# RC_Receiver.net
KiCad netlist of a schematic drawn in EAGLE
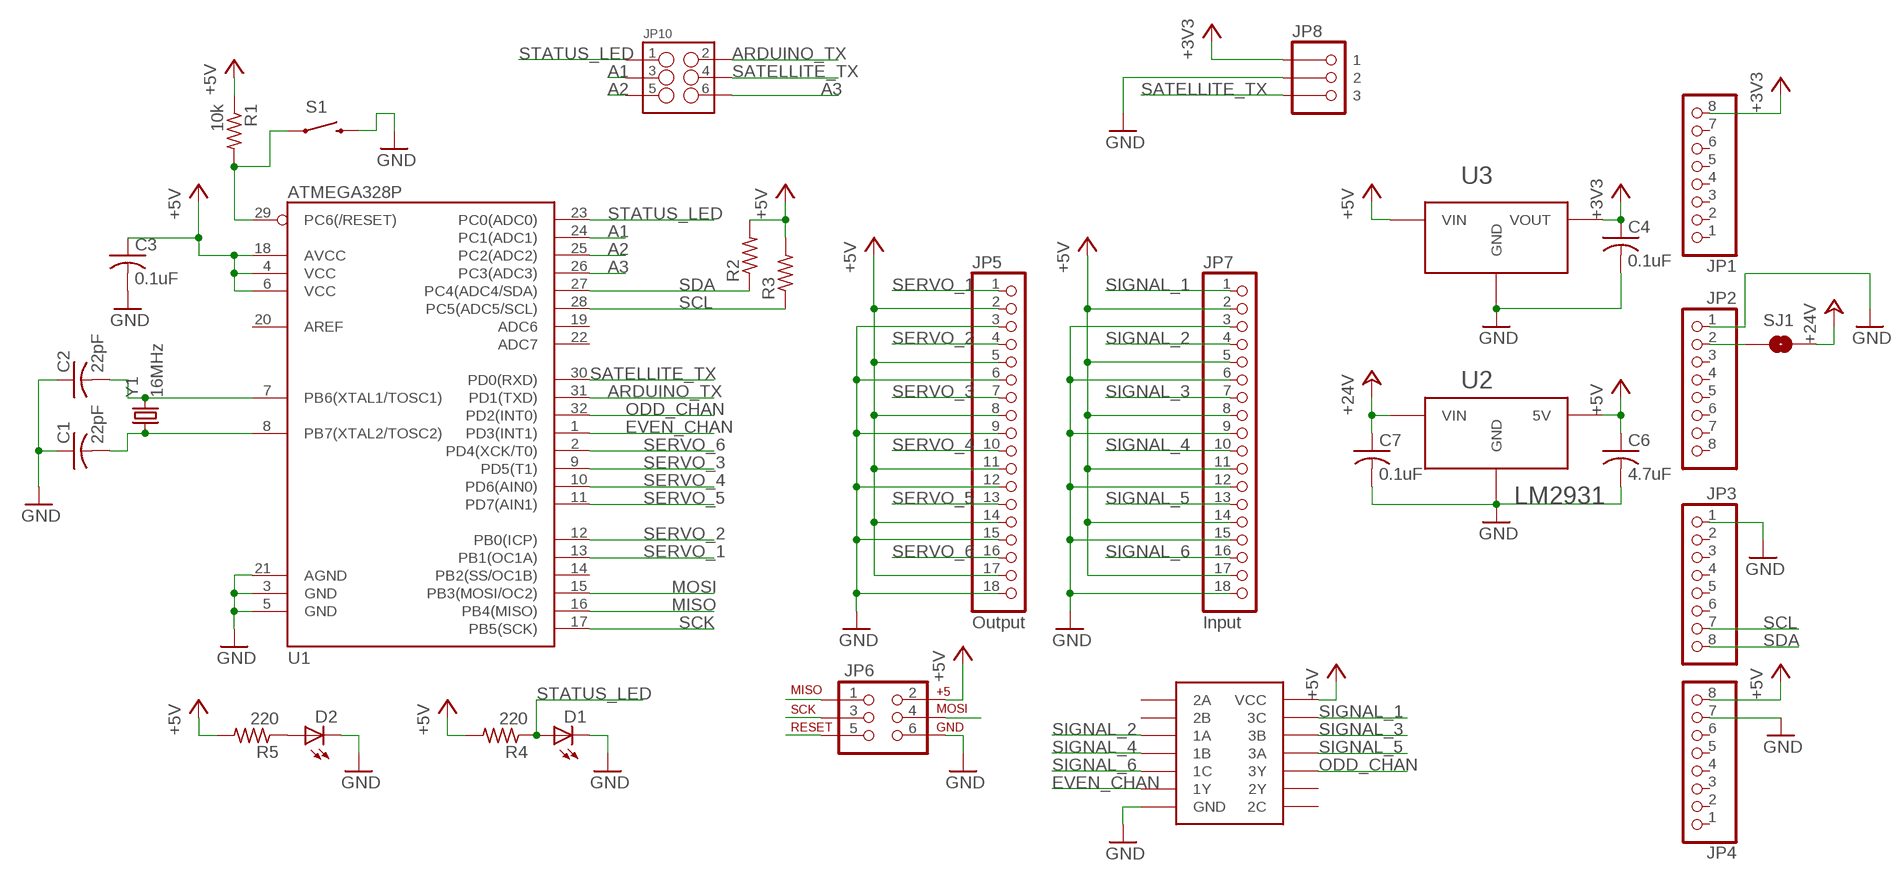
[diagram p0: schematic, sheet 1]

(export (version "E")
  (design (tool "Eeschema 10.0.6"))
  (components
    (comp (ref "C1")
      (value "22pF")
      (footprint "eagle-import:C0603")
      (libsource (lib "eagle-import") (part "C-USC0603"))
    )
    (comp (ref "C2")
      (value "22pF")
      (footprint "eagle-import:C0603")
      (libsource (lib "eagle-import") (part "C-USC0603"))
    )
    (comp (ref "C3")
      (value "0.1uF")
      (footprint "eagle-import:C0603")
      (libsource (lib "eagle-import") (part "C-USC0603"))
    )
    (comp (ref "C4")
      (value "0.1uF")
      (footprint "eagle-import:C0603")
      (libsource (lib "eagle-import") (part "C-USC0603"))
    )
    (comp (ref "C6")
      (value "4.7uF")
      (footprint "eagle-import:C0603")
      (libsource (lib "eagle-import") (part "C-USC0603"))
    )
    (comp (ref "C7")
      (value "0.1uF")
      (footprint "eagle-import:C0603")
      (libsource (lib "eagle-import") (part "C-USC0603"))
    )
    (comp (ref "D1")
      (value "LED-GREENLED-0805_NO_SILK")
      (footprint "eagle-import:LED-0805")
      (libsource (lib "eagle-import") (part "LED-GREENLED-0805_NO_SILK"))
    )
    (comp (ref "D2")
      (value "LED-GREENLED-0805_NO_SILK")
      (footprint "eagle-import:LED-0805")
      (libsource (lib "eagle-import") (part "LED-GREENLED-0805_NO_SILK"))
    )
    (comp (ref "JP1")
      (value "PINHD-1X81X08_NO_SILK")
      (footprint "eagle-import:1X08_NO_SS")
      (libsource (lib "eagle-import") (part "PINHD-1X81X08_NO_SILK"))
    )
    (comp (ref "JP2")
      (value "PINHD-1X81X08_NO_SILK")
      (footprint "eagle-import:1X08_NO_SS")
      (libsource (lib "eagle-import") (part "PINHD-1X81X08_NO_SILK"))
    )
    (comp (ref "JP3")
      (value "PINHD-1X81X08_NO_SILK")
      (footprint "eagle-import:1X08_NO_SS")
      (libsource (lib "eagle-import") (part "PINHD-1X81X08_NO_SILK"))
    )
    (comp (ref "JP4")
      (value "PINHD-1X81X08_NO_SILK")
      (footprint "eagle-import:1X08_NO_SS")
      (libsource (lib "eagle-import") (part "PINHD-1X81X08_NO_SILK"))
    )
    (comp (ref "JP5")
      (value "Output")
      (footprint "eagle-import:3X6_PTH_HEADER")
      (libsource (lib "eagle-import") (part "18_PIN_HEADER3X6_PTH_HEADER"))
    )
    (comp (ref "JP6")
      (value "AVR_SPI_PRG_62X3_LOCK")
      (footprint "eagle-import:2X3_LOCK")
      (libsource (lib "eagle-import") (part "AVR_SPI_PRG_62X3_LOCK"))
    )
    (comp (ref "JP7")
      (value "Input")
      (footprint "eagle-import:3X6_PTH_HEADER")
      (libsource (lib "eagle-import") (part "18_PIN_HEADER3X6_PTH_HEADER"))
    )
    (comp (ref "JP8")
      (value "3-PIN_JST_ZH_PTH_CONNECTORRIGHT_ANGLE_PTH")
      (footprint "eagle-import:3-PIN_JST_ZH_CONNECTOR_TH")
      (fields (field (name "PART#") "455-1670-ND"))
      (libsource (lib "eagle-import") (part "3-PIN_JST_ZH_PTH_CONNECTORRIGHT_ANGLE_PTH"))
    )
    (comp (ref "JP10")
      (value "M03X2NO_SILK")
      (footprint "eagle-import:2X3-NS")
      (libsource (lib "eagle-import") (part "M03X2NO_SILK"))
    )
    (comp (ref "R1")
      (value "10k")
      (footprint "eagle-import:R0603")
      (libsource (lib "eagle-import") (part "R-US_R0603"))
    )
    (comp (ref "R2")
      (value "R-US_R0603")
      (footprint "eagle-import:R0603")
      (libsource (lib "eagle-import") (part "R-US_R0603"))
    )
    (comp (ref "R3")
      (value "R-US_R0603")
      (footprint "eagle-import:R0603")
      (libsource (lib "eagle-import") (part "R-US_R0603"))
    )
    (comp (ref "R4")
      (value "220")
      (footprint "eagle-import:R0603")
      (libsource (lib "eagle-import") (part "R-US_R0603"))
    )
    (comp (ref "R5")
      (value "220")
      (footprint "eagle-import:R0603")
      (libsource (lib "eagle-import") (part "R-US_R0603"))
    )
    (comp (ref "S1")
      (value "SWITCH-MOMENTARY-2SMD")
      (footprint "eagle-import:TACTILE_SWITCH_SMD")
      (libsource (lib "eagle-import") (part "SWITCH-MOMENTARY-2SMD"))
    )
    (comp (ref "SJ1")
      (value "SOLDERJUMPERNC")
      (footprint "eagle-import:SJ_2S")
      (libsource (lib "eagle-import") (part "SOLDERJUMPERNC"))
    )
    (comp (ref "U1")
      (value "ATMEGA328P")
      (footprint "eagle-import:TQFP32-08")
      (libsource (lib "eagle-import") (part "ATMEGA328_SMT"))
    )
    (comp (ref "U2")
      (value "LM2931")
      (footprint "eagle-import:TO263")
      (fields (field (name "PART#") "lm2931"))
      (libsource (lib "eagle-import") (part "LM2931"))
    )
    (comp (ref "U3")
      (value "AP7313SOT23R")
      (footprint "eagle-import:SOT23")
      (fields (field (name "PART#") "AP7313-33SRG-7"))
      (libsource (lib "eagle-import") (part "AP7313SOT23R"))
    )
    (comp (ref "U4")
      (value "C74HC407514-SOIC")
      (footprint "eagle-import:14-SOIC")
      (fields (field (name "PART#") "296-14534-1-ND"))
      (libsource (lib "eagle-import") (part "C74HC407514-SOIC"))
    )
    (comp (ref "Y1")
      (value "16MHz")
      (footprint "eagle-import:CRYSTAL-SMD-5X3")
      (fields (field (name "PART#") "887-1104-1-ND"))
      (libsource (lib "eagle-import") (part "CRYSTAL5X3"))
    )
  )
  (nets
    (net (code "1") (name "+3V3") (class "Default")
      (node (ref "C4") (pin "1") (pinfunction "1_1") (pintype "passive"))
      (node (ref "JP1") (pin "8") (pinfunction "8_8") (pintype "passive"))
      (node (ref "JP8") (pin "P$1") (pinfunction "1_P$1") (pintype "passive"))
      (node (ref "U3") (pin "P$2") (pinfunction "VOUT_P$2") (pintype "bidirectional"))
    )
    (net (code "2") (name "+5V") (class "Default")
      (node (ref "C3") (pin "1") (pinfunction "1_1") (pintype "passive"))
      (node (ref "C6") (pin "1") (pinfunction "1_1") (pintype "passive"))
      (node (ref "JP4") (pin "8") (pinfunction "8_8") (pintype "passive"))
      (node (ref "JP5") (pin "11") (pinfunction "11_11") (pintype "passive"))
      (node (ref "JP5") (pin "14") (pinfunction "14_14") (pintype "passive"))
      (node (ref "JP5") (pin "17") (pinfunction "17_17") (pintype "passive"))
      (node (ref "JP5") (pin "2") (pinfunction "2_2") (pintype "passive"))
      (node (ref "JP5") (pin "5") (pinfunction "5_5") (pintype "passive"))
      (node (ref "JP5") (pin "8") (pinfunction "8_8") (pintype "passive"))
      (node (ref "JP6") (pin "2") (pinfunction "2_2") (pintype "passive"))
      (node (ref "JP7") (pin "11") (pinfunction "11_11") (pintype "passive"))
      (node (ref "JP7") (pin "14") (pinfunction "14_14") (pintype "passive"))
      (node (ref "JP7") (pin "17") (pinfunction "17_17") (pintype "passive"))
      (node (ref "JP7") (pin "2") (pinfunction "2_2") (pintype "passive"))
      (node (ref "JP7") (pin "5") (pinfunction "5_5") (pintype "passive"))
      (node (ref "JP7") (pin "8") (pinfunction "8_8") (pintype "passive"))
      (node (ref "R1") (pin "1") (pinfunction "1_1") (pintype "passive"))
      (node (ref "R2") (pin "2") (pinfunction "2_2") (pintype "passive"))
      (node (ref "R3") (pin "2") (pinfunction "2_2") (pintype "passive"))
      (node (ref "R4") (pin "2") (pinfunction "2_2") (pintype "passive"))
      (node (ref "R5") (pin "2") (pinfunction "2_2") (pintype "passive"))
      (node (ref "U1") (pin "18") (pinfunction "AVCC_18") (pintype "bidirectional"))
      (node (ref "U1") (pin "4") (pinfunction "VCC_4") (pintype "bidirectional"))
      (node (ref "U1") (pin "6") (pinfunction "VCC_6") (pintype "bidirectional"))
      (node (ref "U2") (pin "P$3") (pinfunction "5V_P$3") (pintype "bidirectional"))
      (node (ref "U3") (pin "P$3") (pinfunction "VIN_P$3") (pintype "bidirectional"))
      (node (ref "U4") (pin "P$14") (pinfunction "VCC_P$14") (pintype "power_in"))
    )
    (net (code "3") (name "+24V") (class "Default")
      (node (ref "C7") (pin "1") (pinfunction "1_1") (pintype "passive"))
      (node (ref "SJ1") (pin "2") (pinfunction "2_2") (pintype "passive"))
      (node (ref "U2") (pin "P$2") (pinfunction "VIN_P$2") (pintype "bidirectional"))
    )
    (net (code "4") (name "/A1") (class "Default")
      (node (ref "JP10") (pin "3") (pinfunction "3_3") (pintype "bidirectional"))
      (node (ref "U1") (pin "24") (pinfunction "PC1(ADC1)_24") (pintype "bidirectional"))
    )
    (net (code "5") (name "/A2") (class "Default")
      (node (ref "JP10") (pin "5") (pinfunction "5_5") (pintype "bidirectional"))
      (node (ref "U1") (pin "25") (pinfunction "PC2(ADC2)_25") (pintype "bidirectional"))
    )
    (net (code "6") (name "/A3") (class "Default")
      (node (ref "JP10") (pin "6") (pinfunction "6_6") (pintype "bidirectional"))
      (node (ref "U1") (pin "26") (pinfunction "PC3(ADC3)_26") (pintype "bidirectional"))
    )
    (net (code "7") (name "/ARDUINO_TX") (class "Default")
      (node (ref "JP10") (pin "2") (pinfunction "2_2") (pintype "bidirectional"))
      (node (ref "U1") (pin "31") (pinfunction "PD1(TXD)_31") (pintype "bidirectional"))
    )
    (net (code "8") (name "/EVEN_CHAN") (class "Default")
      (node (ref "U1") (pin "1") (pinfunction "PD3(INT1)_1") (pintype "bidirectional"))
      (node (ref "U4") (pin "P$6") (pinfunction "1Y_P$6") (pintype "bidirectional"))
    )
    (net (code "9") (name "/MISO") (class "Default")
      (node (ref "JP6") (pin "1") (pinfunction "1_1") (pintype "passive"))
      (node (ref "U1") (pin "16") (pinfunction "PB4(MISO)_16") (pintype "bidirectional"))
    )
    (net (code "10") (name "/MOSI") (class "Default")
      (node (ref "JP6") (pin "4") (pinfunction "4_4") (pintype "passive"))
      (node (ref "U1") (pin "15") (pinfunction "PB3(MOSI/OC2)_15") (pintype "bidirectional"))
    )
    (net (code "11") (name "/ODD_CHAN") (class "Default")
      (node (ref "U1") (pin "32") (pinfunction "PD2(INT0)_32") (pintype "bidirectional"))
      (node (ref "U4") (pin "P$10") (pinfunction "3Y_P$10") (pintype "bidirectional"))
    )
    (net (code "12") (name "/RESET") (class "Default")
      (node (ref "JP6") (pin "5") (pinfunction "5_5") (pintype "passive"))
      (node (ref "R1") (pin "2") (pinfunction "2_2") (pintype "passive"))
      (node (ref "S1") (pin "1") (pinfunction "1_1") (pintype "passive"))
      (node (ref "U1") (pin "29") (pinfunction "PC6(/RESET)_29") (pintype "bidirectional"))
    )
    (net (code "13") (name "/SATELLITE_TX") (class "Default")
      (node (ref "JP10") (pin "4") (pinfunction "4_4") (pintype "bidirectional"))
      (node (ref "JP8") (pin "P$3") (pinfunction "3_P$3") (pintype "passive"))
      (node (ref "U1") (pin "30") (pinfunction "PD0(RXD)_30") (pintype "bidirectional"))
    )
    (net (code "14") (name "/SCK") (class "Default")
      (node (ref "JP6") (pin "3") (pinfunction "3_3") (pintype "passive"))
      (node (ref "U1") (pin "17") (pinfunction "PB5(SCK)_17") (pintype "bidirectional"))
    )
    (net (code "15") (name "/SCL") (class "Default")
      (node (ref "JP3") (pin "7") (pinfunction "7_7") (pintype "passive"))
      (node (ref "R3") (pin "1") (pinfunction "1_1") (pintype "passive"))
      (node (ref "U1") (pin "28") (pinfunction "PC5(ADC5/SCL)_28") (pintype "bidirectional"))
    )
    (net (code "16") (name "/SDA") (class "Default")
      (node (ref "JP3") (pin "8") (pinfunction "8_8") (pintype "passive"))
      (node (ref "R2") (pin "1") (pinfunction "1_1") (pintype "passive"))
      (node (ref "U1") (pin "27") (pinfunction "PC4(ADC4/SDA)_27") (pintype "bidirectional"))
    )
    (net (code "17") (name "/SERVO_1") (class "Default")
      (node (ref "JP5") (pin "1") (pinfunction "1_1") (pintype "passive"))
      (node (ref "U1") (pin "13") (pinfunction "PB1(OC1A)_13") (pintype "bidirectional"))
    )
    (net (code "18") (name "/SERVO_2") (class "Default")
      (node (ref "JP5") (pin "4") (pinfunction "4_4") (pintype "passive"))
      (node (ref "U1") (pin "12") (pinfunction "PB0(ICP)_12") (pintype "bidirectional"))
    )
    (net (code "19") (name "/SERVO_3") (class "Default")
      (node (ref "JP5") (pin "7") (pinfunction "7_7") (pintype "passive"))
      (node (ref "U1") (pin "9") (pinfunction "PD5(T1)_9") (pintype "bidirectional"))
    )
    (net (code "20") (name "/SERVO_4") (class "Default")
      (node (ref "JP5") (pin "10") (pinfunction "10_10") (pintype "passive"))
      (node (ref "U1") (pin "10") (pinfunction "PD6(AIN0)_10") (pintype "bidirectional"))
    )
    (net (code "21") (name "/SERVO_5") (class "Default")
      (node (ref "JP5") (pin "13") (pinfunction "13_13") (pintype "passive"))
      (node (ref "U1") (pin "11") (pinfunction "PD7(AIN1)_11") (pintype "bidirectional"))
    )
    (net (code "22") (name "/SERVO_6") (class "Default")
      (node (ref "JP5") (pin "16") (pinfunction "16_16") (pintype "passive"))
      (node (ref "U1") (pin "2") (pinfunction "PD4(XCK/T0)_2") (pintype "bidirectional"))
    )
    (net (code "23") (name "/SIGNAL_1") (class "Default")
      (node (ref "JP7") (pin "1") (pinfunction "1_1") (pintype "passive"))
      (node (ref "U4") (pin "P$13") (pinfunction "3C_P$13") (pintype "bidirectional"))
    )
    (net (code "24") (name "/SIGNAL_2") (class "Default")
      (node (ref "JP7") (pin "4") (pinfunction "4_4") (pintype "passive"))
      (node (ref "U4") (pin "P$3") (pinfunction "1A_P$3") (pintype "bidirectional"))
    )
    (net (code "25") (name "/SIGNAL_3") (class "Default")
      (node (ref "JP7") (pin "7") (pinfunction "7_7") (pintype "passive"))
      (node (ref "U4") (pin "P$12") (pinfunction "3B_P$12") (pintype "bidirectional"))
    )
    (net (code "26") (name "/SIGNAL_4") (class "Default")
      (node (ref "JP7") (pin "10") (pinfunction "10_10") (pintype "passive"))
      (node (ref "U4") (pin "P$4") (pinfunction "1B_P$4") (pintype "bidirectional"))
    )
    (net (code "27") (name "/SIGNAL_5") (class "Default")
      (node (ref "JP7") (pin "13") (pinfunction "13_13") (pintype "passive"))
      (node (ref "U4") (pin "P$11") (pinfunction "3A_P$11") (pintype "bidirectional"))
    )
    (net (code "28") (name "/SIGNAL_6") (class "Default")
      (node (ref "JP7") (pin "16") (pinfunction "16_16") (pintype "passive"))
      (node (ref "U4") (pin "P$5") (pinfunction "1C_P$5") (pintype "bidirectional"))
    )
    (net (code "29") (name "/STATUS_LED") (class "Default")
      (node (ref "D1") (pin "1") (pinfunction "A_1") (pintype "passive"))
      (node (ref "JP10") (pin "1") (pinfunction "1_1") (pintype "bidirectional"))
      (node (ref "R4") (pin "1") (pinfunction "1_1") (pintype "passive"))
      (node (ref "U1") (pin "23") (pinfunction "PC0(ADC0)_23") (pintype "bidirectional"))
    )
    (net (code "30") (name "GND") (class "Default")
      (node (ref "C1") (pin "1") (pinfunction "1_1") (pintype "passive"))
      (node (ref "C2") (pin "1") (pinfunction "1_1") (pintype "passive"))
      (node (ref "C3") (pin "2") (pinfunction "2_2") (pintype "passive"))
      (node (ref "C4") (pin "2") (pinfunction "2_2") (pintype "passive"))
      (node (ref "C6") (pin "2") (pinfunction "2_2") (pintype "passive"))
      (node (ref "C7") (pin "2") (pinfunction "2_2") (pintype "passive"))
      (node (ref "D1") (pin "2") (pinfunction "C_2") (pintype "passive"))
      (node (ref "D2") (pin "2") (pinfunction "C_2") (pintype "passive"))
      (node (ref "JP2") (pin "1") (pinfunction "1_1") (pintype "passive"))
      (node (ref "JP3") (pin "1") (pinfunction "1_1") (pintype "passive"))
      (node (ref "JP4") (pin "7") (pinfunction "7_7") (pintype "passive"))
      (node (ref "JP5") (pin "12") (pinfunction "12_12") (pintype "passive"))
      (node (ref "JP5") (pin "15") (pinfunction "15_15") (pintype "passive"))
      (node (ref "JP5") (pin "18") (pinfunction "18_18") (pintype "passive"))
      (node (ref "JP5") (pin "3") (pinfunction "3_3") (pintype "passive"))
      (node (ref "JP5") (pin "6") (pinfunction "6_6") (pintype "passive"))
      (node (ref "JP5") (pin "9") (pinfunction "9_9") (pintype "passive"))
      (node (ref "JP6") (pin "6") (pinfunction "6_6") (pintype "passive"))
      (node (ref "JP7") (pin "12") (pinfunction "12_12") (pintype "passive"))
      (node (ref "JP7") (pin "15") (pinfunction "15_15") (pintype "passive"))
      (node (ref "JP7") (pin "18") (pinfunction "18_18") (pintype "passive"))
      (node (ref "JP7") (pin "3") (pinfunction "3_3") (pintype "passive"))
      (node (ref "JP7") (pin "6") (pinfunction "6_6") (pintype "passive"))
      (node (ref "JP7") (pin "9") (pinfunction "9_9") (pintype "passive"))
      (node (ref "JP8") (pin "P$2") (pinfunction "2_P$2") (pintype "passive"))
      (node (ref "S1") (pin "3") (pinfunction "2_3") (pintype "passive"))
      (node (ref "U1") (pin "21") (pinfunction "AGND_21") (pintype "bidirectional"))
      (node (ref "U1") (pin "3") (pinfunction "GND_3") (pintype "bidirectional"))
      (node (ref "U1") (pin "5") (pinfunction "GND_5") (pintype "bidirectional"))
      (node (ref "U2") (pin "P$1") (pinfunction "GND_P$1") (pintype "bidirectional"))
      (node (ref "U3") (pin "P$1") (pinfunction "GND_P$1") (pintype "bidirectional"))
      (node (ref "U4") (pin "P$7") (pinfunction "GND_P$7") (pintype "power_in"))
    )
    (net (code "31") (name "Net-(D2-A)") (class "Default")
      (node (ref "D2") (pin "1") (pinfunction "A_1") (pintype "passive"))
      (node (ref "R5") (pin "1") (pinfunction "1_1") (pintype "passive"))
    )
    (net (code "32") (name "Net-(JP2-Pad2)") (class "Default")
      (node (ref "JP2") (pin "2") (pinfunction "2_2") (pintype "passive"))
      (node (ref "SJ1") (pin "1") (pinfunction "1_1") (pintype "passive"))
    )
    (net (code "33") (name "Net-(U1-PB6(XTAL1{slash}TOSC1))") (class "Default")
      (node (ref "C2") (pin "2") (pinfunction "2_2") (pintype "passive"))
      (node (ref "U1") (pin "7") (pinfunction "PB6(XTAL1/TOSC1)_7") (pintype "bidirectional"))
      (node (ref "Y1") (pin "3") (pinfunction "2_3") (pintype "passive"))
    )
    (net (code "34") (name "Net-(U1-PB7(XTAL2{slash}TOSC2))") (class "Default")
      (node (ref "C1") (pin "2") (pinfunction "2_2") (pintype "passive"))
      (node (ref "U1") (pin "8") (pinfunction "PB7(XTAL2/TOSC2)_8") (pintype "bidirectional"))
      (node (ref "Y1") (pin "1") (pinfunction "1_1") (pintype "passive"))
    )
    (net (code "35") (name "unconnected-(JP1-Pad1)") (class "Default")
      (node (ref "JP1") (pin "1") (pinfunction "1_1") (pintype "passive"))
    )
    (net (code "36") (name "unconnected-(JP1-Pad2)") (class "Default")
      (node (ref "JP1") (pin "2") (pinfunction "2_2") (pintype "passive"))
    )
    (net (code "37") (name "unconnected-(JP1-Pad3)") (class "Default")
      (node (ref "JP1") (pin "3") (pinfunction "3_3") (pintype "passive"))
    )
    (net (code "38") (name "unconnected-(JP1-Pad4)") (class "Default")
      (node (ref "JP1") (pin "4") (pinfunction "4_4") (pintype "passive"))
    )
    (net (code "39") (name "unconnected-(JP1-Pad5)") (class "Default")
      (node (ref "JP1") (pin "5") (pinfunction "5_5") (pintype "passive"))
    )
    (net (code "40") (name "unconnected-(JP1-Pad6)") (class "Default")
      (node (ref "JP1") (pin "6") (pinfunction "6_6") (pintype "passive"))
    )
    (net (code "41") (name "unconnected-(JP1-Pad7)") (class "Default")
      (node (ref "JP1") (pin "7") (pinfunction "7_7") (pintype "passive"))
    )
    (net (code "42") (name "unconnected-(JP2-Pad3)") (class "Default")
      (node (ref "JP2") (pin "3") (pinfunction "3_3") (pintype "passive"))
    )
    (net (code "43") (name "unconnected-(JP2-Pad4)") (class "Default")
      (node (ref "JP2") (pin "4") (pinfunction "4_4") (pintype "passive"))
    )
    (net (code "44") (name "unconnected-(JP2-Pad5)") (class "Default")
      (node (ref "JP2") (pin "5") (pinfunction "5_5") (pintype "passive"))
    )
    (net (code "45") (name "unconnected-(JP2-Pad6)") (class "Default")
      (node (ref "JP2") (pin "6") (pinfunction "6_6") (pintype "passive"))
    )
    (net (code "46") (name "unconnected-(JP2-Pad7)") (class "Default")
      (node (ref "JP2") (pin "7") (pinfunction "7_7") (pintype "passive"))
    )
    (net (code "47") (name "unconnected-(JP2-Pad8)") (class "Default")
      (node (ref "JP2") (pin "8") (pinfunction "8_8") (pintype "passive"))
    )
    (net (code "48") (name "unconnected-(JP3-Pad2)") (class "Default")
      (node (ref "JP3") (pin "2") (pinfunction "2_2") (pintype "passive"))
    )
    (net (code "49") (name "unconnected-(JP3-Pad3)") (class "Default")
      (node (ref "JP3") (pin "3") (pinfunction "3_3") (pintype "passive"))
    )
    (net (code "50") (name "unconnected-(JP3-Pad4)") (class "Default")
      (node (ref "JP3") (pin "4") (pinfunction "4_4") (pintype "passive"))
    )
    (net (code "51") (name "unconnected-(JP3-Pad5)") (class "Default")
      (node (ref "JP3") (pin "5") (pinfunction "5_5") (pintype "passive"))
    )
    (net (code "52") (name "unconnected-(JP3-Pad6)") (class "Default")
      (node (ref "JP3") (pin "6") (pinfunction "6_6") (pintype "passive"))
    )
    (net (code "53") (name "unconnected-(JP4-Pad1)") (class "Default")
      (node (ref "JP4") (pin "1") (pinfunction "1_1") (pintype "passive"))
    )
    (net (code "54") (name "unconnected-(JP4-Pad2)") (class "Default")
      (node (ref "JP4") (pin "2") (pinfunction "2_2") (pintype "passive"))
    )
    (net (code "55") (name "unconnected-(JP4-Pad3)") (class "Default")
      (node (ref "JP4") (pin "3") (pinfunction "3_3") (pintype "passive"))
    )
    (net (code "56") (name "unconnected-(JP4-Pad4)") (class "Default")
      (node (ref "JP4") (pin "4") (pinfunction "4_4") (pintype "passive"))
    )
    (net (code "57") (name "unconnected-(JP4-Pad5)") (class "Default")
      (node (ref "JP4") (pin "5") (pinfunction "5_5") (pintype "passive"))
    )
    (net (code "58") (name "unconnected-(JP4-Pad6)") (class "Default")
      (node (ref "JP4") (pin "6") (pinfunction "6_6") (pintype "passive"))
    )
    (net (code "59") (name "unconnected-(U1-ADC6-Pad19)") (class "Default")
      (node (ref "U1") (pin "19") (pinfunction "ADC6_19") (pintype "bidirectional"))
    )
    (net (code "60") (name "unconnected-(U1-ADC7-Pad22)") (class "Default")
      (node (ref "U1") (pin "22") (pinfunction "ADC7_22") (pintype "bidirectional"))
    )
    (net (code "61") (name "unconnected-(U1-AREF-Pad20)") (class "Default")
      (node (ref "U1") (pin "20") (pinfunction "AREF_20") (pintype "bidirectional"))
    )
    (net (code "62") (name "unconnected-(U1-PB2(SS{slash}OC1B)-Pad14)") (class "Default")
      (node (ref "U1") (pin "14") (pinfunction "PB2(SS/OC1B)_14") (pintype "bidirectional"))
    )
    (net (code "63") (name "unconnected-(U4-2A-PadP$1)") (class "Default")
      (node (ref "U4") (pin "P$1") (pinfunction "2A_P$1") (pintype "bidirectional"))
    )
    (net (code "64") (name "unconnected-(U4-2B-PadP$2)") (class "Default")
      (node (ref "U4") (pin "P$2") (pinfunction "2B_P$2") (pintype "bidirectional"))
    )
    (net (code "65") (name "unconnected-(U4-2C-PadP$8)") (class "Default")
      (node (ref "U4") (pin "P$8") (pinfunction "2C_P$8") (pintype "bidirectional"))
    )
    (net (code "66") (name "unconnected-(U4-2Y-PadP$9)") (class "Default")
      (node (ref "U4") (pin "P$9") (pinfunction "2Y_P$9") (pintype "bidirectional"))
    )
  )
)
